# SPI-CAN_Converter.net
KiCad netlist of a schematic drawn in Altium Designer
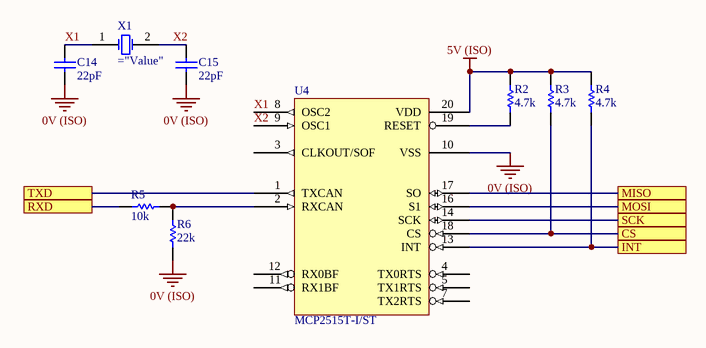
[diagram p0: SPI-CAN Converter.SchDoc]

(export (version "E")
  (design (tool "Eeschema 10.0.6"))
  (components
    (comp (ref "C14")
      (value "22pF")
      (footprint "0805")
      (fields
        (field (name "PART NUMBER") "GRM21A5C2E220JW01D")
        (field (name "TOLERANCE") "±5%")
        (field (name "MANUFACTURER") "muRata")
      )
      (libsource (lib "ts_20-standard-library") (part "Capacitor"))
    )
    (comp (ref "C15")
      (value "22pF")
      (footprint "0805")
      (fields
        (field (name "PART NUMBER") "GRM21A5C2E220JW01D")
        (field (name "TOLERANCE") "±5%")
        (field (name "MANUFACTURER") "muRata")
      )
      (libsource (lib "ts_20-standard-library") (part "Capacitor"))
    )
    (comp (ref "R2")
      (value "4.7k")
      (footprint "0805")
      (fields
        (field (name "PART NUMBER") "RC0805FR074K7L")
        (field (name "MANUFACTURER") "YAGEO")
        (field (name "TOLERANCE") "0.01")
      )
      (libsource (lib "ts_20-standard-library") (part "Resistor"))
    )
    (comp (ref "R3")
      (value "4.7k")
      (footprint "0805")
      (fields
        (field (name "PART NUMBER") "RC0805FR074K7L")
        (field (name "MANUFACTURER") "YAGEO")
        (field (name "TOLERANCE") "0.01")
      )
      (libsource (lib "ts_20-standard-library") (part "Resistor"))
    )
    (comp (ref "R4")
      (value "4.7k")
      (footprint "0805")
      (fields
        (field (name "PART NUMBER") "RC0805FR074K7L")
        (field (name "MANUFACTURER") "YAGEO")
        (field (name "TOLERANCE") "0.01")
      )
      (libsource (lib "ts_20-standard-library") (part "Resistor"))
    )
    (comp (ref "R5")
      (value "10k")
      (footprint "0805")
      (fields
        (field (name "PART NUMBER") "RC0805FR0710KL")
        (field (name "MANUFACTURER") "YAGEO")
        (field (name "TOLERANCE") "0.01")
      )
      (libsource (lib "ts_20-standard-library") (part "Resistor"))
    )
    (comp (ref "R6")
      (value "22k")
      (footprint "0805")
      (fields
        (field (name "PART NUMBER") "RC0805FR0722KL")
        (field (name "MANUFACTURER") "YAGEO")
        (field (name "TOLERANCE") "0.01")
      )
      (libsource (lib "ts_20-standard-library") (part "Resistor"))
    )
    (comp (ref "U4")
      (value "MCP2515T-I/ST")
      (footprint "MCP 20-TSSOP")
      (description "CANbus Controller CAN 2.0 SPI Interface 20-TSSOP")
      (fields
        (field (name "MANUFACTURER") "Microchip Technology")
        (field (name "DIGIKEY PART NUMBER") "MCP2515T-I/STCT-ND")
      )
      (libsource (lib "ts_20-standard-library") (part "MCP2515T"))
    )
    (comp (ref "X1")
      (value "~")
      (footprint "Abracon HC-49/US")
      (fields
        (field (name "PART NUMBER") "ABLS-16.000MHZ-B4-T")
        (field (name "MANUFACTURER") "Abracon LLC")
        (field (name "DIGIKEY PART NUMBER") "535-10226-1-ND")
      )
      (libsource (lib "ts_20-standard-library") (part "Crystal"))
    )
  )
  (nets
    (net (code "1") (name "/CS") (class "Default")
      (node (ref "R3") (pin "1") (pinfunction "1_1") (pintype "passive"))
      (node (ref "U4") (pin "18") (pinfunction "CS_18") (pintype "input"))
    )
    (net (code "2") (name "/INT") (class "Default")
      (node (ref "R4") (pin "1") (pinfunction "1_1") (pintype "passive"))
      (node (ref "U4") (pin "13") (pinfunction "INT_13") (pintype "input"))
    )
    (net (code "3") (name "/MISO") (class "Default")
      (node (ref "U4") (pin "17") (pinfunction "SO_17") (pintype "bidirectional"))
    )
    (net (code "4") (name "/MOSI") (class "Default")
      (node (ref "U4") (pin "16") (pinfunction "S1_16") (pintype "bidirectional"))
    )
    (net (code "5") (name "/RXD") (class "Default")
      (node (ref "R5") (pin "1") (pinfunction "1_1") (pintype "passive"))
    )
    (net (code "6") (name "/SCK") (class "Default")
      (node (ref "U4") (pin "14") (pinfunction "SCK_14") (pintype "bidirectional"))
    )
    (net (code "7") (name "/TXD") (class "Default")
      (node (ref "U4") (pin "1") (pinfunction "TXCAN_1") (pintype "output"))
    )
    (net (code "8") (name "/X1") (class "Default")
      (node (ref "C14") (pin "2") (pinfunction "2_2") (pintype "passive"))
      (node (ref "U4") (pin "8") (pinfunction "OSC2_8") (pintype "output"))
      (node (ref "X1") (pin "1") (pinfunction "OSC1_1") (pintype "passive"))
    )
    (net (code "9") (name "/X2") (class "Default")
      (node (ref "C15") (pin "2") (pinfunction "2_2") (pintype "passive"))
      (node (ref "U4") (pin "9") (pinfunction "OSC1_9") (pintype "input"))
      (node (ref "X1") (pin "2") (pinfunction "OSC2_2") (pintype "passive"))
    )
    (net (code "10") (name "0V (ISO)") (class "Default")
      (node (ref "C14") (pin "1") (pinfunction "1_1") (pintype "passive"))
      (node (ref "C15") (pin "1") (pinfunction "1_1") (pintype "passive"))
      (node (ref "R6") (pin "1") (pinfunction "1_1") (pintype "passive"))
      (node (ref "U4") (pin "10") (pinfunction "VSS_10") (pintype "power_in"))
    )
    (net (code "11") (name "5V (ISO)") (class "Default")
      (node (ref "R2") (pin "2") (pinfunction "2_2") (pintype "passive"))
      (node (ref "R3") (pin "2") (pinfunction "2_2") (pintype "passive"))
      (node (ref "R4") (pin "2") (pinfunction "2_2") (pintype "passive"))
      (node (ref "U4") (pin "20") (pinfunction "VDD_20") (pintype "power_in"))
    )
    (net (code "12") (name "Net-(U4-RESET)") (class "Default")
      (node (ref "R2") (pin "1") (pinfunction "1_1") (pintype "passive"))
      (node (ref "U4") (pin "19") (pinfunction "RESET_19") (pintype "passive"))
    )
    (net (code "13") (name "Net-(U4-RXCAN)") (class "Default")
      (node (ref "R5") (pin "2") (pinfunction "2_2") (pintype "passive"))
      (node (ref "R6") (pin "2") (pinfunction "2_2") (pintype "passive"))
      (node (ref "U4") (pin "2") (pinfunction "RXCAN_2") (pintype "input"))
    )
    (net (code "14") (name "unconnected-(U4-CLKOUT{slash}SOF-Pad3)") (class "Default")
      (node (ref "U4") (pin "3") (pinfunction "CLKOUT/SOF_3") (pintype "output"))
    )
    (net (code "15") (name "unconnected-(U4-RX0BF-Pad12)") (class "Default")
      (node (ref "U4") (pin "12") (pinfunction "RX0BF_12") (pintype "output"))
    )
    (net (code "16") (name "unconnected-(U4-RX1BF-Pad11)") (class "Default")
      (node (ref "U4") (pin "11") (pinfunction "RX1BF_11") (pintype "output"))
    )
    (net (code "17") (name "unconnected-(U4-TX0RTS-Pad4)") (class "Default")
      (node (ref "U4") (pin "4") (pinfunction "TX0RTS_4") (pintype "input"))
    )
    (net (code "18") (name "unconnected-(U4-TX1RTS-Pad5)") (class "Default")
      (node (ref "U4") (pin "5") (pinfunction "TX1RTS_5") (pintype "input"))
    )
    (net (code "19") (name "unconnected-(U4-TX2RTS-Pad7)") (class "Default")
      (node (ref "U4") (pin "7") (pinfunction "TX2RTS_7") (pintype "input"))
    )
  )
)
